# MotorCell.net
KiCad netlist of a schematic drawn in Altium Designer
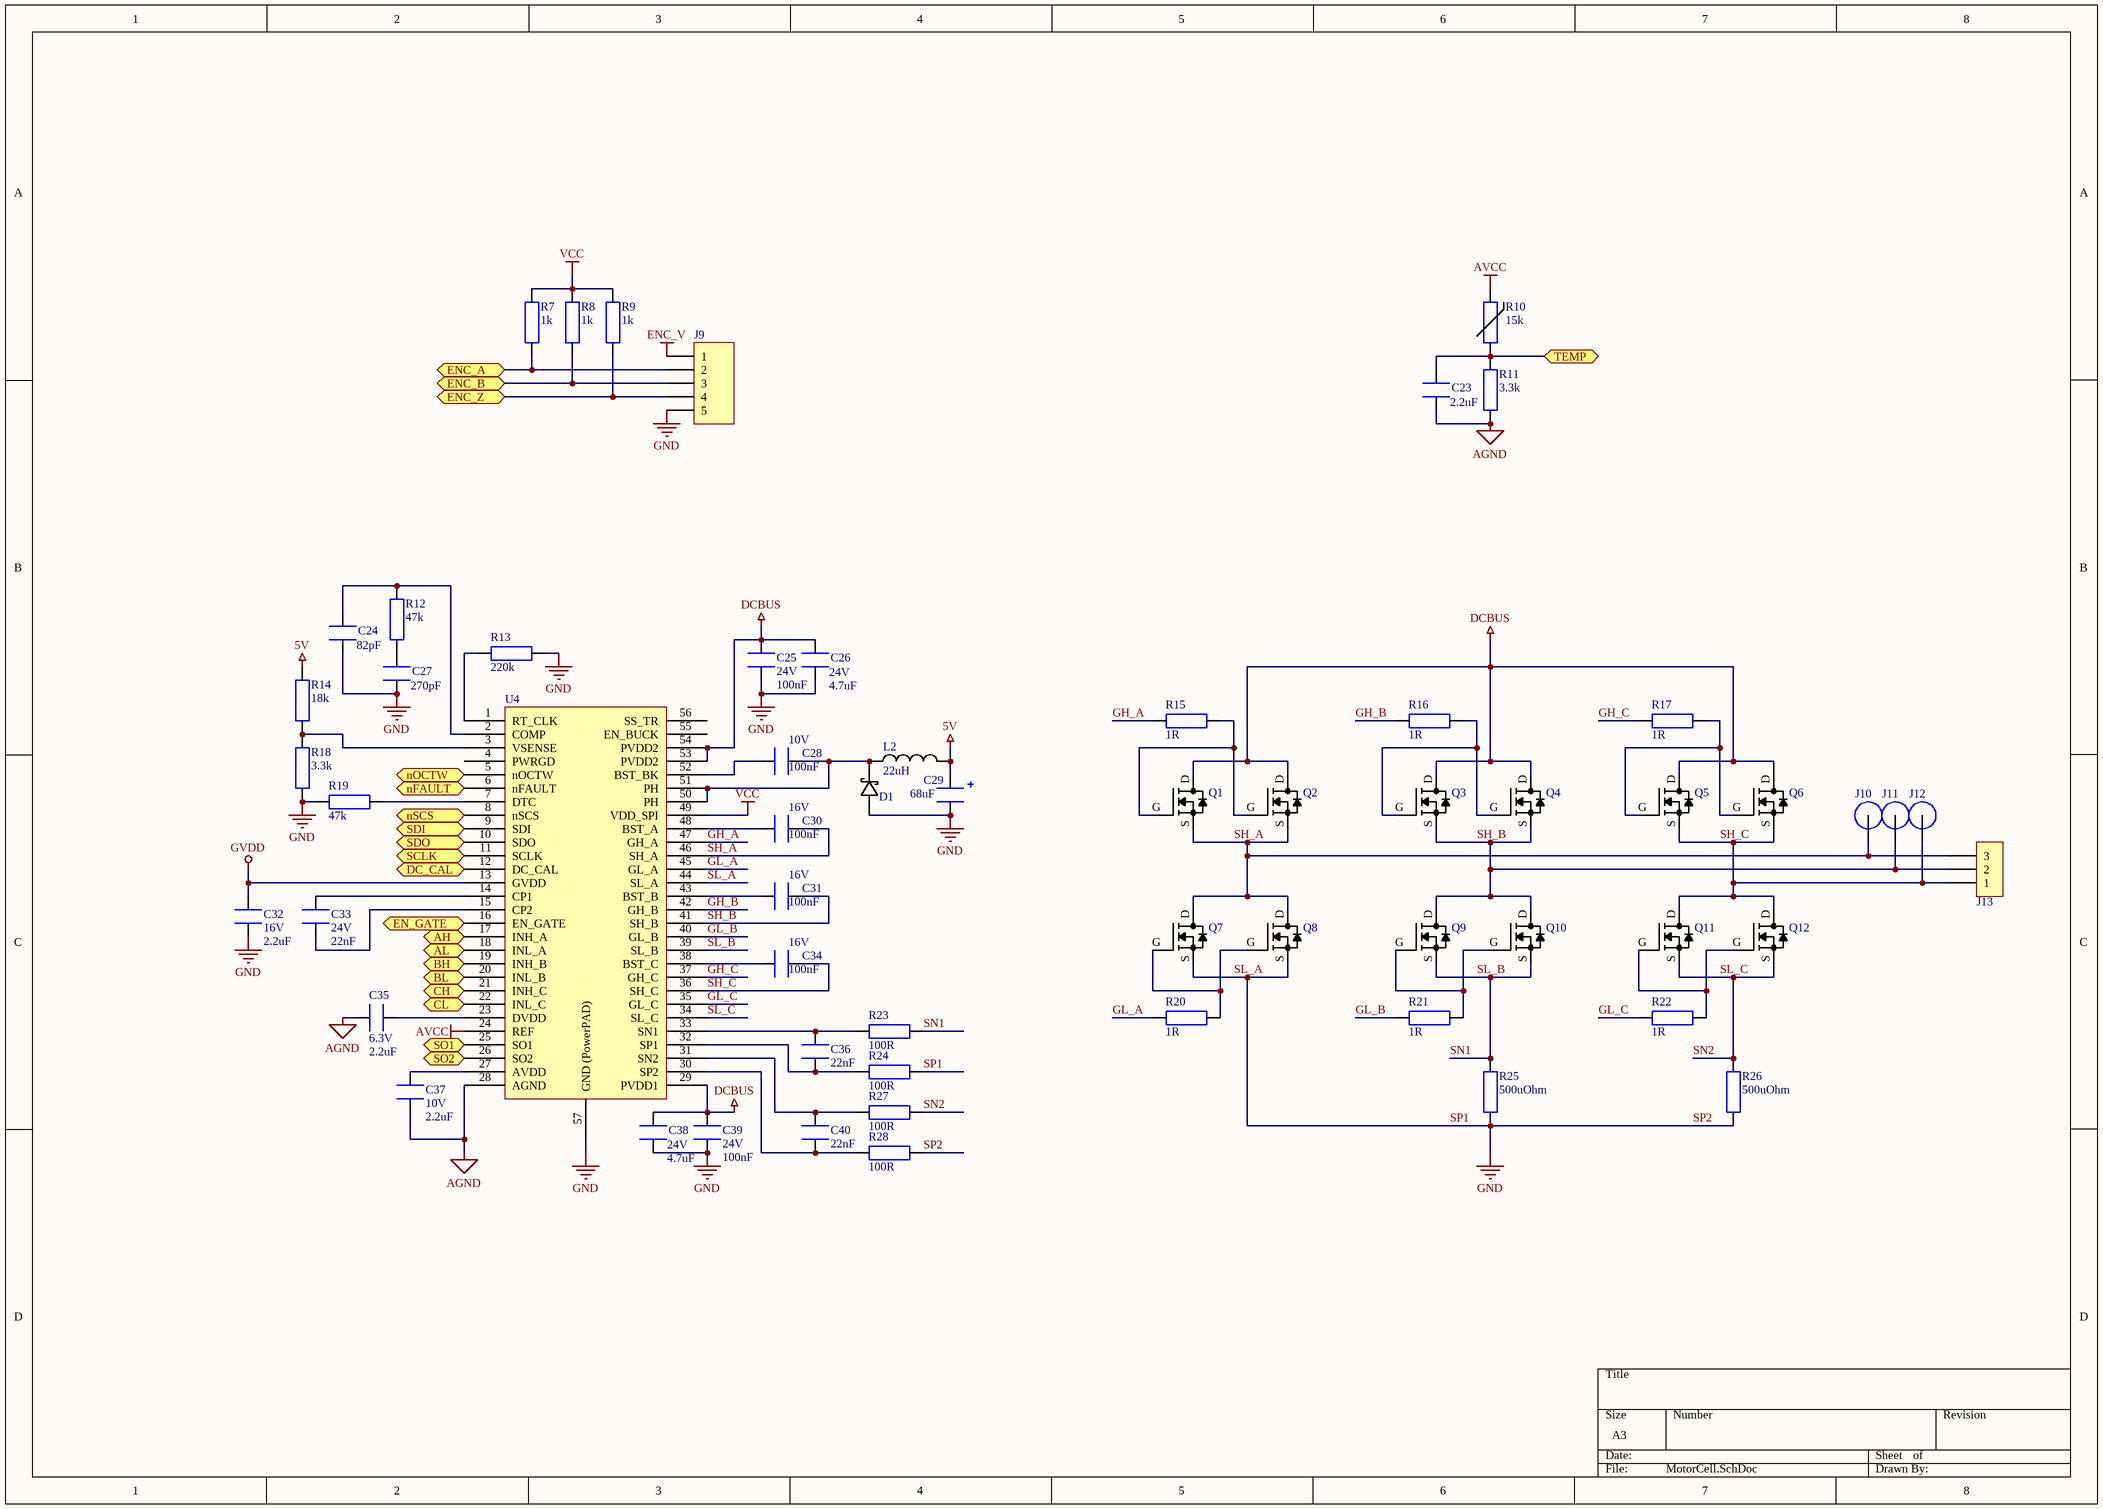
[diagram p0: MotorCell.SchDoc]

(export (version "E")
  (design (tool "Eeschema 10.0.6"))
  (components
    (comp (ref "C23")
      (value "2.2uF")
      (footprint "1608[0603]")
      (description "CAP General 0603")
      (libsource (lib "CustomComponents") (part "CAP_0603"))
    )
    (comp (ref "C24")
      (value "82pF")
      (footprint "1608[0603]")
      (description "CAP General 0603")
      (libsource (lib "CustomComponents") (part "CAP_0603"))
    )
    (comp (ref "C25")
      (value "24V")
      (footprint "1608[0603]")
      (description "CAP General 0603")
      (fields (field (name "ALTIUM_VALUE") "100nF"))
      (libsource (lib "CustomComponents") (part "CAP_0603"))
    )
    (comp (ref "C26")
      (value "24V")
      (footprint "CAPC2012X09N")
      (description "CAP CER 4.7UF 35V X5R 0805")
      (fields (field (name "ALTIUM_VALUE") "4.7uF"))
      (libsource (lib "CustomComponents") (part "GRM219R6YA475KA73D"))
    )
    (comp (ref "C27")
      (value "270pF")
      (footprint "1608[0603]")
      (description "CAP General 0603")
      (libsource (lib "CustomComponents") (part "CAP_0603"))
    )
    (comp (ref "C28")
      (value "10V")
      (footprint "1608[0603]")
      (description "CAP General 0603")
      (fields (field (name "ALTIUM_VALUE") "100nF"))
      (libsource (lib "CustomComponents") (part "CAP_0603"))
    )
    (comp (ref "C29")
      (value "68uF")
      (footprint "CAPCP6032X28N")
      (description "CAP TANT 68UF 16V 20% 2312 250mOhm")
      (libsource (lib "CustomComponents") (part "T495C686M016ATE250"))
    )
    (comp (ref "C30")
      (value "16V")
      (footprint "1608[0603]")
      (description "CAP General 0603")
      (fields (field (name "ALTIUM_VALUE") "100nF"))
      (libsource (lib "CustomComponents") (part "CAP_0603"))
    )
    (comp (ref "C31")
      (value "16V")
      (footprint "1608[0603]")
      (description "CAP General 0603")
      (fields (field (name "ALTIUM_VALUE") "100nF"))
      (libsource (lib "CustomComponents") (part "CAP_0603"))
    )
    (comp (ref "C32")
      (value "16V")
      (footprint "1608[0603]")
      (description "CAP General 0603")
      (fields (field (name "ALTIUM_VALUE") "2.2uF"))
      (libsource (lib "CustomComponents") (part "CAP_0603"))
    )
    (comp (ref "C33")
      (value "24V")
      (footprint "1608[0603]")
      (description "CAP General 0603")
      (fields (field (name "ALTIUM_VALUE") "22nF"))
      (libsource (lib "CustomComponents") (part "CAP_0603"))
    )
    (comp (ref "C34")
      (value "16V")
      (footprint "1608[0603]")
      (description "CAP General 0603")
      (fields (field (name "ALTIUM_VALUE") "100nF"))
      (libsource (lib "CustomComponents") (part "CAP_0603"))
    )
    (comp (ref "C35")
      (value "6.3V")
      (footprint "1608[0603]")
      (description "CAP General 0603")
      (fields (field (name "ALTIUM_VALUE") "2.2uF"))
      (libsource (lib "CustomComponents") (part "CAP_0603"))
    )
    (comp (ref "C36")
      (value "22nF")
      (footprint "1608[0603]")
      (description "CAP General 0603")
      (libsource (lib "CustomComponents") (part "CAP_0603"))
    )
    (comp (ref "C37")
      (value "10V")
      (footprint "1608[0603]")
      (description "CAP General 0603")
      (fields (field (name "ALTIUM_VALUE") "2.2uF"))
      (libsource (lib "CustomComponents") (part "CAP_0603"))
    )
    (comp (ref "C38")
      (value "24V")
      (footprint "CAPC2012X09N")
      (description "CAP CER 4.7UF 35V X5R 0805")
      (fields (field (name "ALTIUM_VALUE") "4.7uF"))
      (libsource (lib "CustomComponents") (part "GRM219R6YA475KA73D"))
    )
    (comp (ref "C39")
      (value "24V")
      (footprint "1608[0603]")
      (description "CAP General 0603")
      (fields (field (name "ALTIUM_VALUE") "100nF"))
      (libsource (lib "CustomComponents") (part "CAP_0603"))
    )
    (comp (ref "C40")
      (value "22nF")
      (footprint "1608[0603]")
      (description "CAP General 0603")
      (libsource (lib "CustomComponents") (part "CAP_0603"))
    )
    (comp (ref "D1")
      (value "~")
      (footprint "DO-214AA")
      (description "DIODE, SCHOTTK, RECTIF, 1A, 30V, SMB")
      (libsource (lib "CustomComponents") (part "SS13B"))
    )
    (comp (ref "J9")
      (value "~")
      (footprint "HDR1X5")
      (description "Header, 5-Pin")
      (fields (field (name "PUBLISHER") "Altium Limited"))
      (libsource (lib "Miscellaneous Connectors") (part "Header 5"))
    )
    (comp (ref "J10")
      (value "~")
      (footprint "M3 Spade Hole")
      (description "M3 Spade Terminal")
      (libsource (lib "CustomComponents") (part "M3 Spade Terminal"))
    )
    (comp (ref "J11")
      (value "~")
      (footprint "M3 Spade Hole")
      (description "M3 Spade Terminal")
      (libsource (lib "CustomComponents") (part "M3 Spade Terminal"))
    )
    (comp (ref "J12")
      (value "~")
      (footprint "M3 Spade Hole")
      (description "M3 Spade Terminal")
      (libsource (lib "CustomComponents") (part "M3 Spade Terminal"))
    )
    (comp (ref "J13")
      (value "~")
      (footprint "MC000051")
      (description "TERMINAL BLOCK, WIRE TO BRD, 3POS, 10AWG")
      (libsource (lib "CustomComponents") (part "MC000051"))
    )
    (comp (ref "L2")
      (value "22uH")
      (footprint "INDC6060X28N")
      (description "INDUCTOR 22UH 1.4A 175.5 MOHM")
      (libsource (lib "CustomComponents") (part "NR6028T220M"))
    )
    (comp (ref "Q1")
      (value "~")
      (footprint "SO8FL")
      (description "MOSFET, N CH, 30V, 70A, SO-8 FL")
      (libsource (lib "CustomComponents") (part "NTMFS4937NT1G"))
    )
    (comp (ref "Q2")
      (value "~")
      (footprint "SO8FL_FILL")
      (description "MOSFET, N CH, 30V, 70A, SO-8 FL")
      (libsource (lib "CustomComponents") (part "NTMFS4937NT1G"))
    )
    (comp (ref "Q3")
      (value "~")
      (footprint "SO8FL")
      (description "MOSFET, N CH, 30V, 70A, SO-8 FL")
      (libsource (lib "CustomComponents") (part "NTMFS4937NT1G"))
    )
    (comp (ref "Q4")
      (value "~")
      (footprint "SO8FL_FILL")
      (description "MOSFET, N CH, 30V, 70A, SO-8 FL")
      (libsource (lib "CustomComponents") (part "NTMFS4937NT1G"))
    )
    (comp (ref "Q5")
      (value "~")
      (footprint "SO8FL")
      (description "MOSFET, N CH, 30V, 70A, SO-8 FL")
      (libsource (lib "CustomComponents") (part "NTMFS4937NT1G"))
    )
    (comp (ref "Q6")
      (value "~")
      (footprint "SO8FL_FILL")
      (description "MOSFET, N CH, 30V, 70A, SO-8 FL")
      (libsource (lib "CustomComponents") (part "NTMFS4937NT1G"))
    )
    (comp (ref "Q7")
      (value "~")
      (footprint "SO8FL")
      (description "MOSFET, N CH, 30V, 70A, SO-8 FL")
      (libsource (lib "CustomComponents") (part "NTMFS4937NT1G"))
    )
    (comp (ref "Q8")
      (value "~")
      (footprint "SO8FL")
      (description "MOSFET, N CH, 30V, 70A, SO-8 FL")
      (libsource (lib "CustomComponents") (part "NTMFS4937NT1G"))
    )
    (comp (ref "Q9")
      (value "~")
      (footprint "SO8FL")
      (description "MOSFET, N CH, 30V, 70A, SO-8 FL")
      (libsource (lib "CustomComponents") (part "NTMFS4937NT1G"))
    )
    (comp (ref "Q10")
      (value "~")
      (footprint "SO8FL")
      (description "MOSFET, N CH, 30V, 70A, SO-8 FL")
      (libsource (lib "CustomComponents") (part "NTMFS4937NT1G"))
    )
    (comp (ref "Q11")
      (value "~")
      (footprint "SO8FL")
      (description "MOSFET, N CH, 30V, 70A, SO-8 FL")
      (libsource (lib "CustomComponents") (part "NTMFS4937NT1G"))
    )
    (comp (ref "Q12")
      (value "~")
      (footprint "SO8FL")
      (description "MOSFET, N CH, 30V, 70A, SO-8 FL")
      (libsource (lib "CustomComponents") (part "NTMFS4937NT1G"))
    )
    (comp (ref "R7")
      (value "1k")
      (footprint "RESC1608X55N")
      (description "RES General 1% 0603")
      (libsource (lib "CustomComponents") (part "RES_0603"))
    )
    (comp (ref "R8")
      (value "1k")
      (footprint "RESC1608X55N")
      (description "RES General 1% 0603")
      (libsource (lib "CustomComponents") (part "RES_0603"))
    )
    (comp (ref "R9")
      (value "1k")
      (footprint "RESC1608X55N")
      (description "RES General 1% 0603")
      (libsource (lib "CustomComponents") (part "RES_0603"))
    )
    (comp (ref "R10")
      (value "15k")
      (footprint "RESC1608X06L")
      (description "THERMISTOR, 15K, 5%, SMD, NTC")
      (libsource (lib "CustomComponents") (part "NTCS0603E3153JMT"))
    )
    (comp (ref "R11")
      (value "3.3k")
      (footprint "RESC1608X55N")
      (description "RES General 1% 0603")
      (libsource (lib "CustomComponents") (part "RES_0603"))
    )
    (comp (ref "R12")
      (value "47k")
      (footprint "RESC1608X55N")
      (description "RES General 1% 0603")
      (libsource (lib "CustomComponents") (part "RES_0603"))
    )
    (comp (ref "R13")
      (value "220k")
      (footprint "RESC1608X55N")
      (description "RES General 1% 0603")
      (libsource (lib "CustomComponents") (part "RES_0603"))
    )
    (comp (ref "R14")
      (value "18k")
      (footprint "RESC1608X55N")
      (description "RES General 1% 0603")
      (libsource (lib "CustomComponents") (part "RES_0603"))
    )
    (comp (ref "R15")
      (value "1R")
      (footprint "RESC1608X55N")
      (description "RES General 1% 0603")
      (libsource (lib "CustomComponents") (part "RES_0603"))
    )
    (comp (ref "R16")
      (value "1R")
      (footprint "RESC1608X55N")
      (description "RES General 1% 0603")
      (libsource (lib "CustomComponents") (part "RES_0603"))
    )
    (comp (ref "R17")
      (value "1R")
      (footprint "RESC1608X55N")
      (description "RES General 1% 0603")
      (libsource (lib "CustomComponents") (part "RES_0603"))
    )
    (comp (ref "R18")
      (value "3.3k")
      (footprint "RESC1608X55N")
      (description "RES General 1% 0603")
      (libsource (lib "CustomComponents") (part "RES_0603"))
    )
    (comp (ref "R19")
      (value "47k")
      (footprint "RESC1608X55N")
      (description "RES General 1% 0603")
      (libsource (lib "CustomComponents") (part "RES_0603"))
    )
    (comp (ref "R20")
      (value "1R")
      (footprint "RESC1608X55N")
      (description "RES General 1% 0603")
      (libsource (lib "CustomComponents") (part "RES_0603"))
    )
    (comp (ref "R21")
      (value "1R")
      (footprint "RESC1608X55N")
      (description "RES General 1% 0603")
      (libsource (lib "CustomComponents") (part "RES_0603"))
    )
    (comp (ref "R22")
      (value "1R")
      (footprint "RESC1608X55N")
      (description "RES General 1% 0603")
      (libsource (lib "CustomComponents") (part "RES_0603"))
    )
    (comp (ref "R23")
      (value "100R")
      (footprint "RESC1608X55N")
      (description "RES General 1% 0603")
      (libsource (lib "CustomComponents") (part "RES_0603"))
    )
    (comp (ref "R24")
      (value "100R")
      (footprint "RESC1608X55N")
      (description "RES General 1% 0603")
      (libsource (lib "CustomComponents") (part "RES_0603"))
    )
    (comp (ref "R25")
      (value "500uOhm")
      (footprint "RESC6432X09N")
      (description "RES SMD 0.0005 OHM 1% 3W 2512")
      (libsource (lib "CustomComponents") (part "CSR2512C0R0005F"))
    )
    (comp (ref "R26")
      (value "500uOhm")
      (footprint "RESC6432X09N")
      (description "RES SMD 0.0005 OHM 1% 3W 2512")
      (libsource (lib "CustomComponents") (part "CSR2512C0R0005F"))
    )
    (comp (ref "R27")
      (value "100R")
      (footprint "RESC1608X55N")
      (description "RES General 1% 0603")
      (libsource (lib "CustomComponents") (part "RES_0603"))
    )
    (comp (ref "R28")
      (value "100R")
      (footprint "RESC1608X55N")
      (description "RES General 1% 0603")
      (libsource (lib "CustomComponents") (part "RES_0603"))
    )
    (comp (ref "U4")
      (value "~")
      (footprint "TSSOP50P810X120_HS-57N")
      (description "MOTOR DRIVER, 3PH, 56HTSSOP")
      (libsource (lib "CustomComponents") (part "DRV8301"))
    )
  )
  (nets
    (net (code "1") (name "/AH") (class "Default")
      (node (ref "U4") (pin "17") (pinfunction "INH_A_17") (pintype "passive"))
    )
    (net (code "2") (name "/AL") (class "Default")
      (node (ref "U4") (pin "18") (pinfunction "INL_A_18") (pintype "passive"))
    )
    (net (code "3") (name "/BH") (class "Default")
      (node (ref "U4") (pin "19") (pinfunction "INH_B_19") (pintype "passive"))
    )
    (net (code "4") (name "/BL") (class "Default")
      (node (ref "U4") (pin "20") (pinfunction "INL_B_20") (pintype "passive"))
    )
    (net (code "5") (name "/CH") (class "Default")
      (node (ref "U4") (pin "21") (pinfunction "INH_C_21") (pintype "passive"))
    )
    (net (code "6") (name "/CL") (class "Default")
      (node (ref "U4") (pin "22") (pinfunction "INL_C_22") (pintype "passive"))
    )
    (net (code "7") (name "/DC_CAL") (class "Default")
      (node (ref "U4") (pin "12") (pinfunction "DC_CAL_12") (pintype "passive"))
    )
    (net (code "8") (name "/ENC_A") (class "Default")
      (node (ref "J9") (pin "2") (pinfunction "2_2") (pintype "passive"))
      (node (ref "R7") (pin "2") (pinfunction "0_2") (pintype "passive"))
    )
    (net (code "9") (name "/ENC_B") (class "Default")
      (node (ref "J9") (pin "3") (pinfunction "3_3") (pintype "passive"))
      (node (ref "R8") (pin "2") (pinfunction "0_2") (pintype "passive"))
    )
    (net (code "10") (name "/ENC_Z") (class "Default")
      (node (ref "J9") (pin "4") (pinfunction "4_4") (pintype "passive"))
      (node (ref "R9") (pin "2") (pinfunction "0_2") (pintype "passive"))
    )
    (net (code "11") (name "/EN_GATE") (class "Default")
      (node (ref "U4") (pin "16") (pinfunction "EN_GATE_16") (pintype "passive"))
    )
    (net (code "12") (name "/GH_A") (class "Default")
      (node (ref "R15") (pin "1") (pinfunction "0_1") (pintype "passive"))
      (node (ref "U4") (pin "47") (pinfunction "GH_A_47") (pintype "passive"))
    )
    (net (code "13") (name "/GH_B") (class "Default")
      (node (ref "R16") (pin "1") (pinfunction "0_1") (pintype "passive"))
      (node (ref "U4") (pin "42") (pinfunction "GH_B_42") (pintype "passive"))
    )
    (net (code "14") (name "/GH_C") (class "Default")
      (node (ref "R17") (pin "1") (pinfunction "0_1") (pintype "passive"))
      (node (ref "U4") (pin "37") (pinfunction "GH_C_37") (pintype "passive"))
    )
    (net (code "15") (name "/GL_A") (class "Default")
      (node (ref "R20") (pin "1") (pinfunction "0_1") (pintype "passive"))
      (node (ref "U4") (pin "45") (pinfunction "GL_A_45") (pintype "passive"))
    )
    (net (code "16") (name "/GL_B") (class "Default")
      (node (ref "R21") (pin "1") (pinfunction "0_1") (pintype "passive"))
      (node (ref "U4") (pin "40") (pinfunction "GL_B_40") (pintype "passive"))
    )
    (net (code "17") (name "/GL_C") (class "Default")
      (node (ref "R22") (pin "1") (pinfunction "0_1") (pintype "passive"))
      (node (ref "U4") (pin "35") (pinfunction "GL_C_35") (pintype "passive"))
    )
    (net (code "18") (name "/SCLK") (class "Default")
      (node (ref "U4") (pin "11") (pinfunction "SCLK_11") (pintype "passive"))
    )
    (net (code "19") (name "/SDI") (class "Default")
      (node (ref "U4") (pin "9") (pinfunction "SDI_9") (pintype "passive"))
    )
    (net (code "20") (name "/SDO") (class "Default")
      (node (ref "U4") (pin "10") (pinfunction "SDO_10") (pintype "passive"))
    )
    (net (code "21") (name "/SH_A") (class "Default")
      (node (ref "C30") (pin "1") (pinfunction "1_1") (pintype "passive"))
      (node (ref "J10") (pin "1") (pinfunction "1_1") (pintype "passive"))
      (node (ref "J13") (pin "3") (pinfunction "3_3") (pintype "passive"))
      (node (ref "Q1") (pin "S") (pinfunction "S_S") (pintype "passive"))
      (node (ref "Q2") (pin "S") (pinfunction "S_S") (pintype "passive"))
      (node (ref "Q7") (pin "D") (pinfunction "D_D") (pintype "passive"))
      (node (ref "Q8") (pin "D") (pinfunction "D_D") (pintype "passive"))
      (node (ref "U4") (pin "46") (pinfunction "SH_A_46") (pintype "passive"))
    )
    (net (code "22") (name "/SH_B") (class "Default")
      (node (ref "C31") (pin "1") (pinfunction "1_1") (pintype "passive"))
      (node (ref "J11") (pin "1") (pinfunction "1_1") (pintype "passive"))
      (node (ref "J13") (pin "2") (pinfunction "2_2") (pintype "passive"))
      (node (ref "Q10") (pin "D") (pinfunction "D_D") (pintype "passive"))
      (node (ref "Q3") (pin "S") (pinfunction "S_S") (pintype "passive"))
      (node (ref "Q4") (pin "S") (pinfunction "S_S") (pintype "passive"))
      (node (ref "Q9") (pin "D") (pinfunction "D_D") (pintype "passive"))
      (node (ref "U4") (pin "41") (pinfunction "SH_B_41") (pintype "passive"))
    )
    (net (code "23") (name "/SH_C") (class "Default")
      (node (ref "C34") (pin "1") (pinfunction "1_1") (pintype "passive"))
      (node (ref "J12") (pin "1") (pinfunction "1_1") (pintype "passive"))
      (node (ref "J13") (pin "1") (pinfunction "1_1") (pintype "passive"))
      (node (ref "Q11") (pin "D") (pinfunction "D_D") (pintype "passive"))
      (node (ref "Q12") (pin "D") (pinfunction "D_D") (pintype "passive"))
      (node (ref "Q5") (pin "S") (pinfunction "S_S") (pintype "passive"))
      (node (ref "Q6") (pin "S") (pinfunction "S_S") (pintype "passive"))
      (node (ref "U4") (pin "36") (pinfunction "SH_C_36") (pintype "passive"))
    )
    (net (code "24") (name "/SL_B") (class "Default")
      (node (ref "Q10") (pin "S") (pinfunction "S_S") (pintype "passive"))
      (node (ref "Q9") (pin "S") (pinfunction "S_S") (pintype "passive"))
      (node (ref "R23") (pin "1") (pinfunction "0_1") (pintype "passive"))
      (node (ref "R25") (pin "2") (pinfunction "0_2") (pintype "passive"))
      (node (ref "U4") (pin "39") (pinfunction "SL_B_39") (pintype "passive"))
    )
    (net (code "25") (name "/SL_C") (class "Default")
      (node (ref "Q11") (pin "S") (pinfunction "S_S") (pintype "passive"))
      (node (ref "Q12") (pin "S") (pinfunction "S_S") (pintype "passive"))
      (node (ref "R26") (pin "2") (pinfunction "0_2") (pintype "passive"))
      (node (ref "R27") (pin "1") (pinfunction "0_1") (pintype "passive"))
      (node (ref "U4") (pin "34") (pinfunction "SL_C_34") (pintype "passive"))
    )
    (net (code "26") (name "/SO1") (class "Default")
      (node (ref "U4") (pin "25") (pinfunction "SO1_25") (pintype "passive"))
    )
    (net (code "27") (name "/SO2") (class "Default")
      (node (ref "U4") (pin "26") (pinfunction "SO2_26") (pintype "passive"))
    )
    (net (code "28") (name "/TEMP") (class "Default")
      (node (ref "C23") (pin "2") (pinfunction "2_2") (pintype "passive"))
      (node (ref "R10") (pin "1") (pinfunction "0_1") (pintype "passive"))
      (node (ref "R11") (pin "1") (pinfunction "0_1") (pintype "passive"))
    )
    (net (code "29") (name "/nFAULT") (class "Default")
      (node (ref "U4") (pin "6") (pinfunction "nFAULT_6") (pintype "passive"))
    )
    (net (code "30") (name "/nOCTW") (class "Default")
      (node (ref "U4") (pin "5") (pinfunction "nOCTW_5") (pintype "passive"))
    )
    (net (code "31") (name "/nSCS") (class "Default")
      (node (ref "U4") (pin "8") (pinfunction "nSCS_8") (pintype "passive"))
    )
    (net (code "32") (name "5V") (class "Default")
      (node (ref "C29") (pin "1") (pinfunction "1_1") (pintype "passive"))
      (node (ref "L2") (pin "2") (pinfunction "2_2") (pintype "passive"))
      (node (ref "R14") (pin "1") (pinfunction "0_1") (pintype "passive"))
    )
    (net (code "33") (name "AGND") (class "Default")
      (node (ref "C23") (pin "1") (pinfunction "1_1") (pintype "passive"))
      (node (ref "C35") (pin "1") (pinfunction "1_1") (pintype "passive"))
      (node (ref "C37") (pin "1") (pinfunction "1_1") (pintype "passive"))
      (node (ref "R11") (pin "2") (pinfunction "0_2") (pintype "passive"))
      (node (ref "U4") (pin "28") (pinfunction "AGND_28") (pintype "passive"))
    )
    (net (code "34") (name "AVCC") (class "Default")
      (node (ref "R10") (pin "2") (pinfunction "0_2") (pintype "passive"))
      (node (ref "U4") (pin "24") (pinfunction "REF_24") (pintype "passive"))
    )
    (net (code "35") (name "DCBUS") (class "Default")
      (node (ref "C25") (pin "1") (pinfunction "1_1") (pintype "passive"))
      (node (ref "C26") (pin "2") (pinfunction "2_2") (pintype "passive"))
      (node (ref "C38") (pin "2") (pinfunction "2_2") (pintype "passive"))
      (node (ref "C39") (pin "1") (pinfunction "1_1") (pintype "passive"))
      (node (ref "Q1") (pin "D") (pinfunction "D_D") (pintype "passive"))
      (node (ref "Q2") (pin "D") (pinfunction "D_D") (pintype "passive"))
      (node (ref "Q3") (pin "D") (pinfunction "D_D") (pintype "passive"))
      (node (ref "Q4") (pin "D") (pinfunction "D_D") (pintype "passive"))
      (node (ref "Q5") (pin "D") (pinfunction "D_D") (pintype "passive"))
      (node (ref "Q6") (pin "D") (pinfunction "D_D") (pintype "passive"))
      (node (ref "U4") (pin "29") (pinfunction "PVDD1_29") (pintype "passive"))
      (node (ref "U4") (pin "53") (pinfunction "PVDD2_53") (pintype "passive"))
      (node (ref "U4") (pin "54") (pinfunction "PVDD2_54") (pintype "passive"))
    )
    (net (code "36") (name "ENC_V") (class "Default")
      (node (ref "J9") (pin "1") (pinfunction "1_1") (pintype "passive"))
    )
    (net (code "37") (name "GND") (class "Default")
      (node (ref "C24") (pin "2") (pinfunction "2_2") (pintype "passive"))
      (node (ref "C25") (pin "2") (pinfunction "2_2") (pintype "passive"))
      (node (ref "C26") (pin "1") (pinfunction "1_1") (pintype "passive"))
      (node (ref "C27") (pin "2") (pinfunction "2_2") (pintype "passive"))
      (node (ref "C29") (pin "2") (pinfunction "2_2") (pintype "passive"))
      (node (ref "C32") (pin "1") (pinfunction "1_1") (pintype "passive"))
      (node (ref "C38") (pin "1") (pinfunction "1_1") (pintype "passive"))
      (node (ref "C39") (pin "2") (pinfunction "2_2") (pintype "passive"))
      (node (ref "D1") (pin "A") (pinfunction "A_A") (pintype "passive"))
      (node (ref "J9") (pin "5") (pinfunction "5_5") (pintype "passive"))
      (node (ref "Q7") (pin "S") (pinfunction "S_S") (pintype "passive"))
      (node (ref "Q8") (pin "S") (pinfunction "S_S") (pintype "passive"))
      (node (ref "R13") (pin "2") (pinfunction "0_2") (pintype "passive"))
      (node (ref "R18") (pin "2") (pinfunction "0_2") (pintype "passive"))
      (node (ref "R19") (pin "2") (pinfunction "0_2") (pintype "passive"))
      (node (ref "R24") (pin "1") (pinfunction "0_1") (pintype "passive"))
      (node (ref "R25") (pin "1") (pinfunction "0_1") (pintype "passive"))
      (node (ref "R26") (pin "1") (pinfunction "0_1") (pintype "passive"))
      (node (ref "R28") (pin "1") (pinfunction "0_1") (pintype "passive"))
      (node (ref "U4") (pin "44") (pinfunction "SL_A_44") (pintype "passive"))
      (node (ref "U4") (pin "57") (pinfunction "GND_(PowerPAD)_57") (pintype "passive"))
    )
    (net (code "38") (name "GVDD") (class "Default")
      (node (ref "C32") (pin "2") (pinfunction "2_2") (pintype "passive"))
      (node (ref "U4") (pin "13") (pinfunction "GVDD_13") (pintype "passive"))
    )
    (net (code "39") (name "Net-(C27-Pad1)") (class "Default")
      (node (ref "C27") (pin "1") (pinfunction "1_1") (pintype "passive"))
      (node (ref "R12") (pin "2") (pinfunction "0_2") (pintype "passive"))
    )
    (net (code "40") (name "Net-(C28-Pad1)") (class "Default")
      (node (ref "C28") (pin "1") (pinfunction "1_1") (pintype "passive"))
      (node (ref "D1") (pin "K") (pinfunction "K_K") (pintype "passive"))
      (node (ref "L2") (pin "1") (pinfunction "1_1") (pintype "passive"))
      (node (ref "U4") (pin "50") (pinfunction "PH_50") (pintype "passive"))
      (node (ref "U4") (pin "51") (pinfunction "PH_51") (pintype "passive"))
    )
    (net (code "41") (name "Net-(Q1-PadG)") (class "Default")
      (node (ref "Q1") (pin "G") (pinfunction "G_G") (pintype "passive"))
      (node (ref "Q2") (pin "G") (pinfunction "G_G") (pintype "passive"))
      (node (ref "R15") (pin "2") (pinfunction "0_2") (pintype "passive"))
    )
    (net (code "42") (name "Net-(Q3-PadG)") (class "Default")
      (node (ref "Q3") (pin "G") (pinfunction "G_G") (pintype "passive"))
      (node (ref "Q4") (pin "G") (pinfunction "G_G") (pintype "passive"))
      (node (ref "R16") (pin "2") (pinfunction "0_2") (pintype "passive"))
    )
    (net (code "43") (name "Net-(Q5-PadG)") (class "Default")
      (node (ref "Q5") (pin "G") (pinfunction "G_G") (pintype "passive"))
      (node (ref "Q6") (pin "G") (pinfunction "G_G") (pintype "passive"))
      (node (ref "R17") (pin "2") (pinfunction "0_2") (pintype "passive"))
    )
    (net (code "44") (name "Net-(Q7-PadG)") (class "Default")
      (node (ref "Q7") (pin "G") (pinfunction "G_G") (pintype "passive"))
      (node (ref "Q8") (pin "G") (pinfunction "G_G") (pintype "passive"))
      (node (ref "R20") (pin "2") (pinfunction "0_2") (pintype "passive"))
    )
    (net (code "45") (name "Net-(Q10-PadG)") (class "Default")
      (node (ref "Q10") (pin "G") (pinfunction "G_G") (pintype "passive"))
      (node (ref "Q9") (pin "G") (pinfunction "G_G") (pintype "passive"))
      (node (ref "R21") (pin "2") (pinfunction "0_2") (pintype "passive"))
    )
    (net (code "46") (name "Net-(Q11-PadG)") (class "Default")
      (node (ref "Q11") (pin "G") (pinfunction "G_G") (pintype "passive"))
      (node (ref "Q12") (pin "G") (pinfunction "G_G") (pintype "passive"))
      (node (ref "R22") (pin "2") (pinfunction "0_2") (pintype "passive"))
    )
    (net (code "47") (name "Net-(U4-AVDD)") (class "Default")
      (node (ref "C37") (pin "2") (pinfunction "2_2") (pintype "passive"))
      (node (ref "U4") (pin "27") (pinfunction "AVDD_27") (pintype "passive"))
    )
    (net (code "48") (name "Net-(U4-BST_A)") (class "Default")
      (node (ref "C30") (pin "2") (pinfunction "2_2") (pintype "passive"))
      (node (ref "U4") (pin "48") (pinfunction "BST_A_48") (pintype "passive"))
    )
    (net (code "49") (name "Net-(U4-BST_B)") (class "Default")
      (node (ref "C31") (pin "2") (pinfunction "2_2") (pintype "passive"))
      (node (ref "U4") (pin "43") (pinfunction "BST_B_43") (pintype "passive"))
    )
    (net (code "50") (name "Net-(U4-BST_BK)") (class "Default")
      (node (ref "C28") (pin "2") (pinfunction "2_2") (pintype "passive"))
      (node (ref "U4") (pin "52") (pinfunction "BST_BK_52") (pintype "passive"))
    )
    (net (code "51") (name "Net-(U4-BST_C)") (class "Default")
      (node (ref "C34") (pin "2") (pinfunction "2_2") (pintype "passive"))
      (node (ref "U4") (pin "38") (pinfunction "BST_C_38") (pintype "passive"))
    )
    (net (code "52") (name "Net-(U4-COMP)") (class "Default")
      (node (ref "C24") (pin "1") (pinfunction "1_1") (pintype "passive"))
      (node (ref "R12") (pin "1") (pinfunction "0_1") (pintype "passive"))
      (node (ref "U4") (pin "2") (pinfunction "COMP_2") (pintype "passive"))
    )
    (net (code "53") (name "Net-(U4-CP1)") (class "Default")
      (node (ref "C33") (pin "1") (pinfunction "1_1") (pintype "passive"))
      (node (ref "U4") (pin "14") (pinfunction "CP1_14") (pintype "passive"))
    )
    (net (code "54") (name "Net-(U4-CP2)") (class "Default")
      (node (ref "C33") (pin "2") (pinfunction "2_2") (pintype "passive"))
      (node (ref "U4") (pin "15") (pinfunction "CP2_15") (pintype "passive"))
    )
    (net (code "55") (name "Net-(U4-DTC)") (class "Default")
      (node (ref "R19") (pin "1") (pinfunction "0_1") (pintype "passive"))
      (node (ref "U4") (pin "7") (pinfunction "DTC_7") (pintype "passive"))
    )
    (net (code "56") (name "Net-(U4-DVDD)") (class "Default")
      (node (ref "C35") (pin "2") (pinfunction "2_2") (pintype "passive"))
      (node (ref "U4") (pin "23") (pinfunction "DVDD_23") (pintype "passive"))
    )
    (net (code "57") (name "Net-(U4-RT_CLK)") (class "Default")
      (node (ref "R13") (pin "1") (pinfunction "0_1") (pintype "passive"))
      (node (ref "U4") (pin "1") (pinfunction "RT_CLK_1") (pintype "passive"))
    )
    (net (code "58") (name "Net-(U4-SN1)") (class "Default")
      (node (ref "C36") (pin "1") (pinfunction "1_1") (pintype "passive"))
      (node (ref "R23") (pin "2") (pinfunction "0_2") (pintype "passive"))
      (node (ref "U4") (pin "33") (pinfunction "SN1_33") (pintype "passive"))
    )
    (net (code "59") (name "Net-(U4-SN2)") (class "Default")
      (node (ref "C40") (pin "1") (pinfunction "1_1") (pintype "passive"))
      (node (ref "R27") (pin "2") (pinfunction "0_2") (pintype "passive"))
      (node (ref "U4") (pin "31") (pinfunction "SN2_31") (pintype "passive"))
    )
    (net (code "60") (name "Net-(U4-SP1)") (class "Default")
      (node (ref "C36") (pin "2") (pinfunction "2_2") (pintype "passive"))
      (node (ref "R24") (pin "2") (pinfunction "0_2") (pintype "passive"))
      (node (ref "U4") (pin "32") (pinfunction "SP1_32") (pintype "passive"))
    )
    (net (code "61") (name "Net-(U4-SP2)") (class "Default")
      (node (ref "C40") (pin "2") (pinfunction "2_2") (pintype "passive"))
      (node (ref "R28") (pin "2") (pinfunction "0_2") (pintype "passive"))
      (node (ref "U4") (pin "30") (pinfunction "SP2_30") (pintype "passive"))
    )
    (net (code "62") (name "Net-(U4-VSENSE)") (class "Default")
      (node (ref "R14") (pin "2") (pinfunction "0_2") (pintype "passive"))
      (node (ref "R18") (pin "1") (pinfunction "0_1") (pintype "passive"))
      (node (ref "U4") (pin "3") (pinfunction "VSENSE_3") (pintype "passive"))
    )
    (net (code "63") (name "VCC") (class "Default")
      (node (ref "R7") (pin "1") (pinfunction "0_1") (pintype "passive"))
      (node (ref "R8") (pin "1") (pinfunction "0_1") (pintype "passive"))
      (node (ref "R9") (pin "1") (pinfunction "0_1") (pintype "passive"))
      (node (ref "U4") (pin "49") (pinfunction "VDD_SPI_49") (pintype "passive"))
    )
    (net (code "64") (name "unconnected-(U4-EN_BUCK-Pad55)") (class "Default")
      (node (ref "U4") (pin "55") (pinfunction "EN_BUCK_55") (pintype "passive"))
    )
    (net (code "65") (name "unconnected-(U4-PWRGD-Pad4)") (class "Default")
      (node (ref "U4") (pin "4") (pinfunction "PWRGD_4") (pintype "passive"))
    )
    (net (code "66") (name "unconnected-(U4-SS_TR-Pad56)") (class "Default")
      (node (ref "U4") (pin "56") (pinfunction "SS_TR_56") (pintype "passive"))
    )
  )
)
